# Nixie_ver1.net
KiCad netlist of a schematic drawn in EAGLE
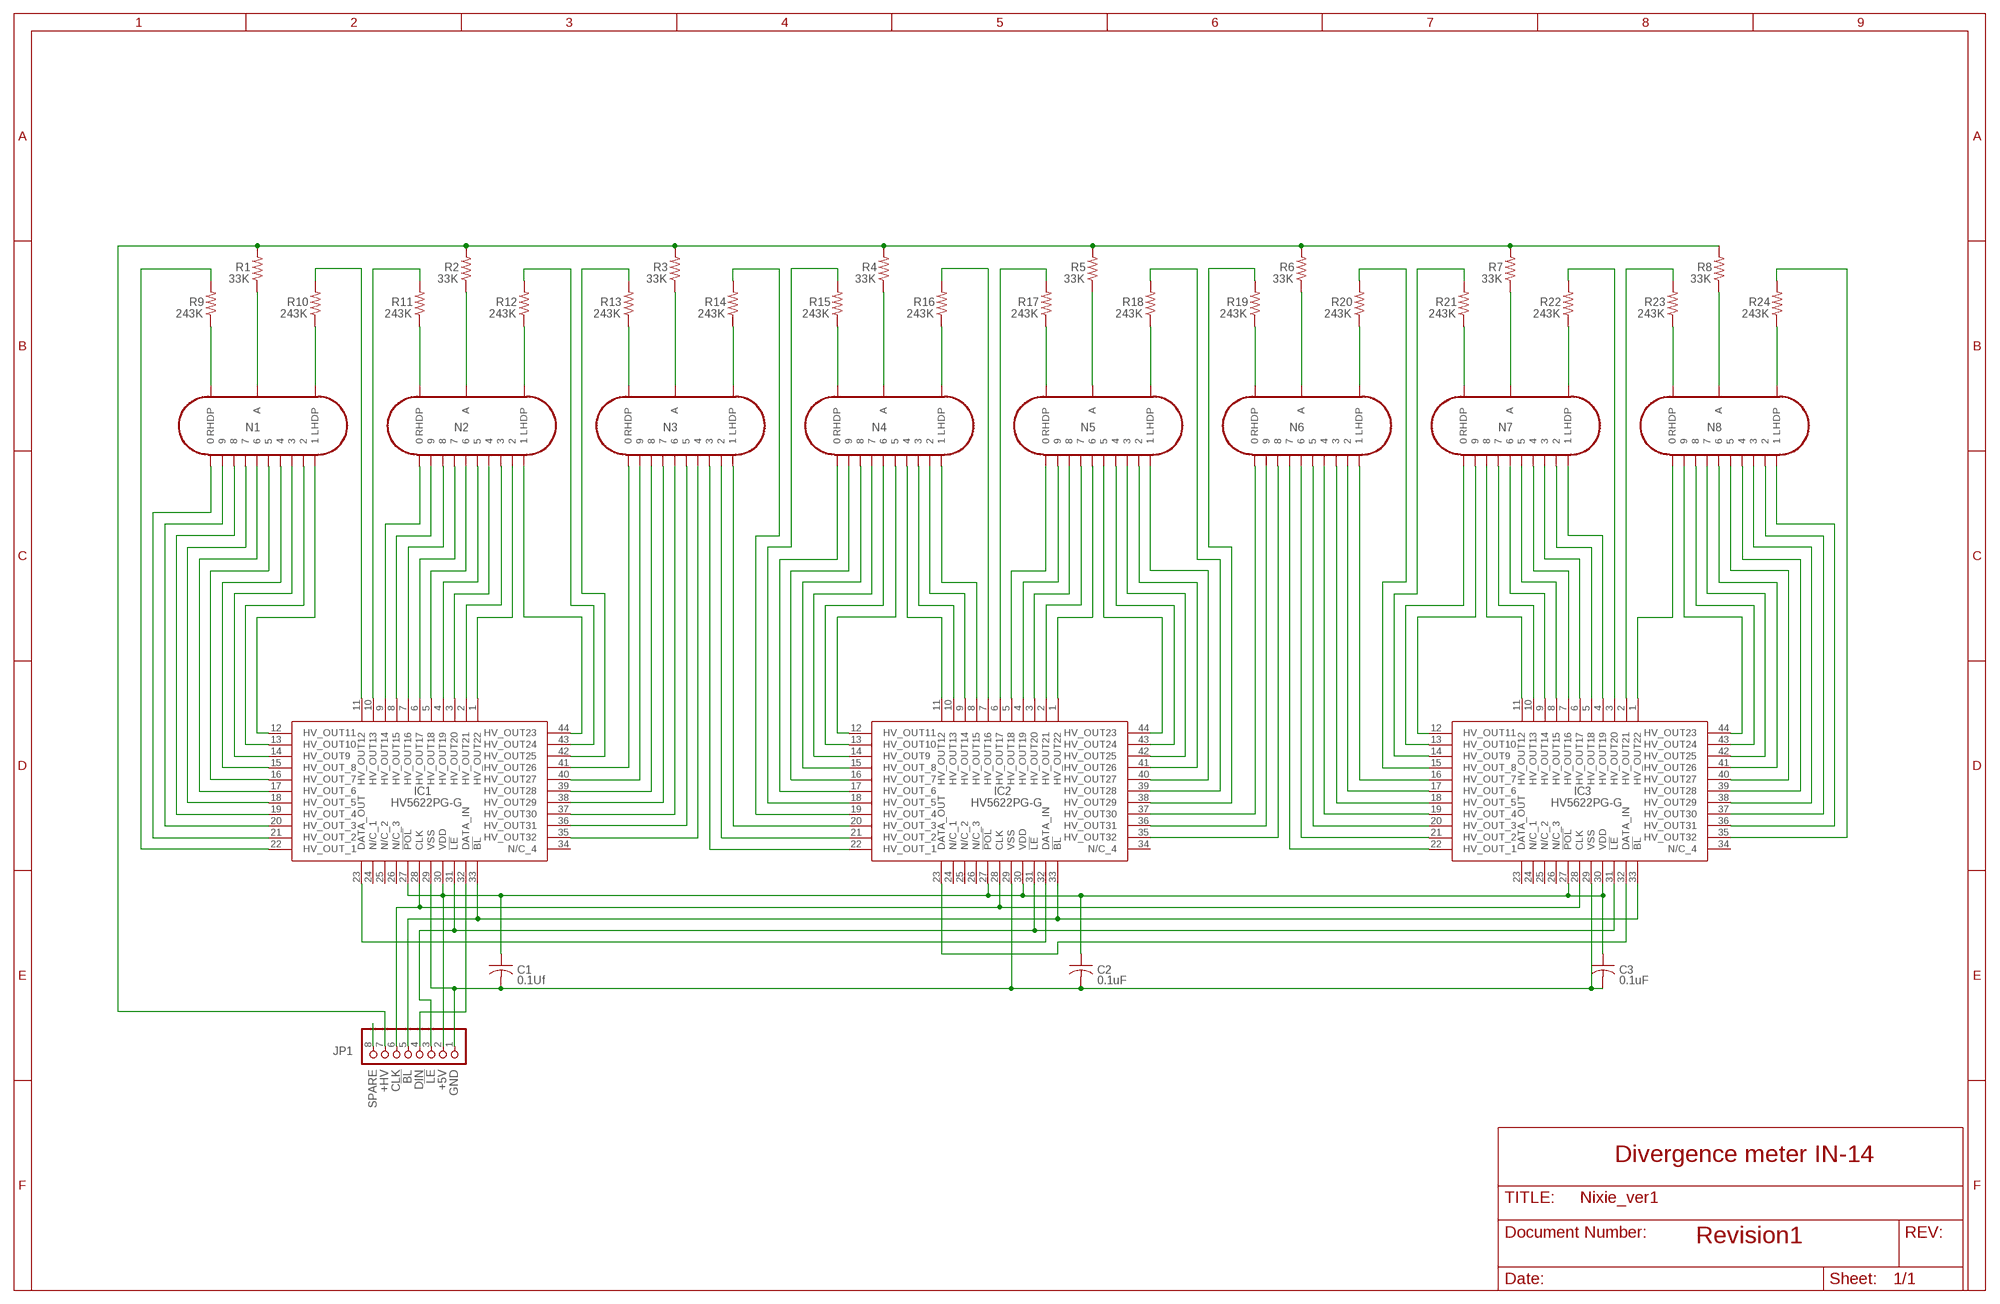
[diagram p0: schematic, sheet 1]

(export (version "E")
  (design (tool "Eeschema 10.0.6"))
  (components
    (comp (ref "C1")
      (value "0.1Uf")
      (footprint "eagle-import:C025-024X044")
      (libsource (lib "eagle-import") (part "C-US025-024X044"))
    )
    (comp (ref "C2")
      (value "0.1uF")
      (footprint "eagle-import:C025-024X044")
      (libsource (lib "eagle-import") (part "C-US025-024X044"))
    )
    (comp (ref "C3")
      (value "0.1uF")
      (footprint "eagle-import:C025-024X044")
      (libsource (lib "eagle-import") (part "C-US025-024X044"))
    )
    (comp (ref "IC1")
      (value "HV5622PG-G")
      (footprint "eagle-import:QFP80P1390X1390X235-44N")
      (fields (field (name "MOUSER_PART_NUMBER") "689-HV5622PG-G"))
      (libsource (lib "eagle-import") (part "HV5622PG-G"))
    )
    (comp (ref "IC2")
      (value "HV5622PG-G")
      (footprint "eagle-import:QFP80P1390X1390X235-44N")
      (fields (field (name "MOUSER_PART_NUMBER") "689-HV5622PG-G"))
      (libsource (lib "eagle-import") (part "HV5622PG-G"))
    )
    (comp (ref "IC3")
      (value "HV5622PG-G")
      (footprint "eagle-import:QFP80P1390X1390X235-44N")
      (fields (field (name "MOUSER_PART_NUMBER") "689-HV5622PG-G"))
      (libsource (lib "eagle-import") (part "HV5622PG-G"))
    )
    (comp (ref "JP1")
      (value "PINHD-1X8")
      (footprint "eagle-import:1X08")
      (libsource (lib "eagle-import") (part "PINHD-1X8"))
    )
    (comp (ref "N1")
      (value "IN-14")
      (footprint "eagle-import:IN-14")
      (libsource (lib "eagle-import") (part "IN-14"))
    )
    (comp (ref "N2")
      (value "IN-14")
      (footprint "eagle-import:IN-14")
      (libsource (lib "eagle-import") (part "IN-14"))
    )
    (comp (ref "N3")
      (value "IN-14")
      (footprint "eagle-import:IN-14")
      (libsource (lib "eagle-import") (part "IN-14"))
    )
    (comp (ref "N4")
      (value "IN-14")
      (footprint "eagle-import:IN-14")
      (libsource (lib "eagle-import") (part "IN-14"))
    )
    (comp (ref "N5")
      (value "IN-14")
      (footprint "eagle-import:IN-14")
      (libsource (lib "eagle-import") (part "IN-14"))
    )
    (comp (ref "N6")
      (value "IN-14")
      (footprint "eagle-import:IN-14")
      (libsource (lib "eagle-import") (part "IN-14"))
    )
    (comp (ref "N7")
      (value "IN-14")
      (footprint "eagle-import:IN-14")
      (libsource (lib "eagle-import") (part "IN-14"))
    )
    (comp (ref "N8")
      (value "IN-14")
      (footprint "eagle-import:IN-14")
      (libsource (lib "eagle-import") (part "IN-14"))
    )
    (comp (ref "R1")
      (value "33K")
      (footprint "eagle-import:0204_7")
      (libsource (lib "eagle-import") (part "R-US_0204/7"))
    )
    (comp (ref "R2")
      (value "33K")
      (footprint "eagle-import:0204_7")
      (libsource (lib "eagle-import") (part "R-US_0204/7"))
    )
    (comp (ref "R3")
      (value "33K")
      (footprint "eagle-import:0204_7")
      (libsource (lib "eagle-import") (part "R-US_0204/7"))
    )
    (comp (ref "R4")
      (value "33K")
      (footprint "eagle-import:0204_7")
      (libsource (lib "eagle-import") (part "R-US_0204/7"))
    )
    (comp (ref "R5")
      (value "33K")
      (footprint "eagle-import:0204_7")
      (libsource (lib "eagle-import") (part "R-US_0204/7"))
    )
    (comp (ref "R6")
      (value "33K")
      (footprint "eagle-import:0204_7")
      (libsource (lib "eagle-import") (part "R-US_0204/7"))
    )
    (comp (ref "R7")
      (value "33K")
      (footprint "eagle-import:0204_7")
      (libsource (lib "eagle-import") (part "R-US_0204/7"))
    )
    (comp (ref "R8")
      (value "33K")
      (footprint "eagle-import:0204_7")
      (libsource (lib "eagle-import") (part "R-US_0204/7"))
    )
    (comp (ref "R9")
      (value "243K")
      (footprint "eagle-import:0204_7")
      (libsource (lib "eagle-import") (part "R-US_0204/7"))
    )
    (comp (ref "R10")
      (value "243K")
      (footprint "eagle-import:0204_7")
      (libsource (lib "eagle-import") (part "R-US_0204/7"))
    )
    (comp (ref "R11")
      (value "243K")
      (footprint "eagle-import:0204_7")
      (libsource (lib "eagle-import") (part "R-US_0204/7"))
    )
    (comp (ref "R12")
      (value "243K")
      (footprint "eagle-import:0204_7")
      (libsource (lib "eagle-import") (part "R-US_0204/7"))
    )
    (comp (ref "R13")
      (value "243K")
      (footprint "eagle-import:0204_7")
      (libsource (lib "eagle-import") (part "R-US_0204/7"))
    )
    (comp (ref "R14")
      (value "243K")
      (footprint "eagle-import:0204_7")
      (libsource (lib "eagle-import") (part "R-US_0204/7"))
    )
    (comp (ref "R15")
      (value "243K")
      (footprint "eagle-import:0204_7")
      (libsource (lib "eagle-import") (part "R-US_0204/7"))
    )
    (comp (ref "R16")
      (value "243K")
      (footprint "eagle-import:0204_7")
      (libsource (lib "eagle-import") (part "R-US_0204/7"))
    )
    (comp (ref "R17")
      (value "243K")
      (footprint "eagle-import:0204_7")
      (libsource (lib "eagle-import") (part "R-US_0204/7"))
    )
    (comp (ref "R18")
      (value "243K")
      (footprint "eagle-import:0204_7")
      (libsource (lib "eagle-import") (part "R-US_0204/7"))
    )
    (comp (ref "R19")
      (value "243K")
      (footprint "eagle-import:0204_7")
      (libsource (lib "eagle-import") (part "R-US_0204/7"))
    )
    (comp (ref "R20")
      (value "243K")
      (footprint "eagle-import:0204_7")
      (libsource (lib "eagle-import") (part "R-US_0204/7"))
    )
    (comp (ref "R21")
      (value "243K")
      (footprint "eagle-import:0204_7")
      (libsource (lib "eagle-import") (part "R-US_0204/7"))
    )
    (comp (ref "R22")
      (value "243K")
      (footprint "eagle-import:0204_7")
      (libsource (lib "eagle-import") (part "R-US_0204/7"))
    )
    (comp (ref "R23")
      (value "243K")
      (footprint "eagle-import:0204_7")
      (libsource (lib "eagle-import") (part "R-US_0204/7"))
    )
    (comp (ref "R24")
      (value "243K")
      (footprint "eagle-import:0204_7")
      (libsource (lib "eagle-import") (part "R-US_0204/7"))
    )
  )
  (nets
    (net (code "1") (name "/+5V") (class "Default")
      (node (ref "C1") (pin "1") (pinfunction "1_1") (pintype "passive"))
      (node (ref "C2") (pin "1") (pinfunction "1_1") (pintype "passive"))
      (node (ref "C3") (pin "1") (pinfunction "1_1") (pintype "passive"))
      (node (ref "IC1") (pin "27") (pinfunction "~{POL}_27") (pintype "bidirectional"))
      (node (ref "IC1") (pin "30") (pinfunction "VDD_30") (pintype "bidirectional"))
      (node (ref "IC2") (pin "27") (pinfunction "~{POL}_27") (pintype "bidirectional"))
      (node (ref "IC2") (pin "30") (pinfunction "VDD_30") (pintype "bidirectional"))
      (node (ref "IC3") (pin "27") (pinfunction "~{POL}_27") (pintype "bidirectional"))
      (node (ref "IC3") (pin "30") (pinfunction "VDD_30") (pintype "bidirectional"))
      (node (ref "JP1") (pin "2") (pinfunction "2_2") (pintype "passive"))
    )
    (net (code "2") (name "/+HV") (class "Default")
      (node (ref "JP1") (pin "7") (pinfunction "7_7") (pintype "passive"))
      (node (ref "R1") (pin "2") (pinfunction "2_2") (pintype "passive"))
      (node (ref "R2") (pin "2") (pinfunction "2_2") (pintype "passive"))
      (node (ref "R3") (pin "2") (pinfunction "2_2") (pintype "passive"))
      (node (ref "R4") (pin "2") (pinfunction "2_2") (pintype "passive"))
      (node (ref "R5") (pin "2") (pinfunction "2_2") (pintype "passive"))
      (node (ref "R6") (pin "2") (pinfunction "2_2") (pintype "passive"))
      (node (ref "R7") (pin "2") (pinfunction "2_2") (pintype "passive"))
      (node (ref "R8") (pin "2") (pinfunction "2_2") (pintype "passive"))
    )
    (net (code "3") (name "/CLK") (class "Default")
      (node (ref "IC1") (pin "28") (pinfunction "CLK_28") (pintype "bidirectional"))
      (node (ref "IC2") (pin "28") (pinfunction "CLK_28") (pintype "bidirectional"))
      (node (ref "IC3") (pin "28") (pinfunction "CLK_28") (pintype "bidirectional"))
      (node (ref "JP1") (pin "6") (pinfunction "6_6") (pintype "passive"))
    )
    (net (code "4") (name "/DIN") (class "Default")
      (node (ref "IC1") (pin "32") (pinfunction "DATA_IN_32") (pintype "bidirectional"))
      (node (ref "JP1") (pin "4") (pinfunction "4_4") (pintype "passive"))
    )
    (net (code "5") (name "/GND") (class "Default")
      (node (ref "C1") (pin "2") (pinfunction "2_2") (pintype "passive"))
      (node (ref "C2") (pin "2") (pinfunction "2_2") (pintype "passive"))
      (node (ref "C3") (pin "2") (pinfunction "2_2") (pintype "passive"))
      (node (ref "IC1") (pin "29") (pinfunction "VSS_29") (pintype "bidirectional"))
      (node (ref "IC2") (pin "29") (pinfunction "VSS_29") (pintype "bidirectional"))
      (node (ref "IC3") (pin "29") (pinfunction "VSS_29") (pintype "bidirectional"))
      (node (ref "JP1") (pin "1") (pinfunction "1_1") (pintype "passive"))
    )
    (net (code "6") (name "/SPARE") (class "Default")
      (node (ref "JP1") (pin "8") (pinfunction "8_8") (pintype "passive"))
    )
    (net (code "7") (name "/~{BL}") (class "Default")
      (node (ref "IC1") (pin "33") (pinfunction "~{BL}_33") (pintype "bidirectional"))
      (node (ref "IC2") (pin "33") (pinfunction "~{BL}_33") (pintype "bidirectional"))
      (node (ref "IC3") (pin "33") (pinfunction "~{BL}_33") (pintype "bidirectional"))
      (node (ref "JP1") (pin "5") (pinfunction "5_5") (pintype "passive"))
    )
    (net (code "8") (name "/~{LE}") (class "Default")
      (node (ref "IC1") (pin "31") (pinfunction "~{LE}_31") (pintype "bidirectional"))
      (node (ref "IC2") (pin "31") (pinfunction "~{LE}_31") (pintype "bidirectional"))
      (node (ref "IC3") (pin "31") (pinfunction "~{LE}_31") (pintype "bidirectional"))
      (node (ref "JP1") (pin "3") (pinfunction "3_3") (pintype "passive"))
    )
    (net (code "9") (name "Net-(IC1-DATA_OUT)") (class "Default")
      (node (ref "IC1") (pin "23") (pinfunction "DATA_OUT_23") (pintype "bidirectional"))
      (node (ref "IC2") (pin "32") (pinfunction "DATA_IN_32") (pintype "bidirectional"))
    )
    (net (code "10") (name "Net-(IC1-HV_OUT9)") (class "Default")
      (node (ref "IC1") (pin "14") (pinfunction "HV_OUT9_14") (pintype "bidirectional"))
      (node (ref "N1") (pin "3") (pinfunction "3_3") (pintype "bidirectional"))
    )
    (net (code "11") (name "Net-(IC1-HV_OUT10)") (class "Default")
      (node (ref "IC1") (pin "13") (pinfunction "HV_OUT10_13") (pintype "bidirectional"))
      (node (ref "N1") (pin "2") (pinfunction "2_2") (pintype "bidirectional"))
    )
    (net (code "12") (name "Net-(IC1-HV_OUT11)") (class "Default")
      (node (ref "IC1") (pin "12") (pinfunction "HV_OUT11_12") (pintype "bidirectional"))
      (node (ref "N1") (pin "1") (pinfunction "1_1") (pintype "bidirectional"))
    )
    (net (code "13") (name "Net-(IC1-HV_OUT12)") (class "Default")
      (node (ref "IC1") (pin "11") (pinfunction "HV_OUT12_11") (pintype "bidirectional"))
      (node (ref "R10") (pin "2") (pinfunction "2_2") (pintype "passive"))
    )
    (net (code "14") (name "Net-(IC1-HV_OUT13)") (class "Default")
      (node (ref "IC1") (pin "10") (pinfunction "HV_OUT13_10") (pintype "bidirectional"))
      (node (ref "R11") (pin "2") (pinfunction "2_2") (pintype "passive"))
    )
    (net (code "15") (name "Net-(IC1-HV_OUT14)") (class "Default")
      (node (ref "IC1") (pin "9") (pinfunction "HV_OUT14_9") (pintype "bidirectional"))
      (node (ref "N2") (pin "0") (pinfunction "0_0") (pintype "bidirectional"))
    )
    (net (code "16") (name "Net-(IC1-HV_OUT15)") (class "Default")
      (node (ref "IC1") (pin "8") (pinfunction "HV_OUT15_8") (pintype "bidirectional"))
      (node (ref "N2") (pin "9") (pinfunction "9_9") (pintype "bidirectional"))
    )
    (net (code "17") (name "Net-(IC1-HV_OUT16)") (class "Default")
      (node (ref "IC1") (pin "7") (pinfunction "HV_OUT16_7") (pintype "bidirectional"))
      (node (ref "N2") (pin "8") (pinfunction "8_8") (pintype "bidirectional"))
    )
    (net (code "18") (name "Net-(IC1-HV_OUT17)") (class "Default")
      (node (ref "IC1") (pin "6") (pinfunction "HV_OUT17_6") (pintype "bidirectional"))
      (node (ref "N2") (pin "7") (pinfunction "7_7") (pintype "bidirectional"))
    )
    (net (code "19") (name "Net-(IC1-HV_OUT18)") (class "Default")
      (node (ref "IC1") (pin "5") (pinfunction "HV_OUT18_5") (pintype "bidirectional"))
      (node (ref "N2") (pin "6") (pinfunction "6_6") (pintype "bidirectional"))
    )
    (net (code "20") (name "Net-(IC1-HV_OUT19)") (class "Default")
      (node (ref "IC1") (pin "4") (pinfunction "HV_OUT19_4") (pintype "bidirectional"))
      (node (ref "N2") (pin "5") (pinfunction "5_5") (pintype "bidirectional"))
    )
    (net (code "21") (name "Net-(IC1-HV_OUT20)") (class "Default")
      (node (ref "IC1") (pin "3") (pinfunction "HV_OUT20_3") (pintype "bidirectional"))
      (node (ref "N2") (pin "4") (pinfunction "4_4") (pintype "bidirectional"))
    )
    (net (code "22") (name "Net-(IC1-HV_OUT21)") (class "Default")
      (node (ref "IC1") (pin "2") (pinfunction "HV_OUT21_2") (pintype "bidirectional"))
      (node (ref "N2") (pin "3") (pinfunction "3_3") (pintype "bidirectional"))
    )
    (net (code "23") (name "Net-(IC1-HV_OUT22)") (class "Default")
      (node (ref "IC1") (pin "1") (pinfunction "HV_OUT22_1") (pintype "bidirectional"))
      (node (ref "N2") (pin "2") (pinfunction "2_2") (pintype "bidirectional"))
    )
    (net (code "24") (name "Net-(IC1-HV_OUT23)") (class "Default")
      (node (ref "IC1") (pin "44") (pinfunction "HV_OUT23_44") (pintype "bidirectional"))
      (node (ref "N2") (pin "1") (pinfunction "1_1") (pintype "bidirectional"))
    )
    (net (code "25") (name "Net-(IC1-HV_OUT24)") (class "Default")
      (node (ref "IC1") (pin "43") (pinfunction "HV_OUT24_43") (pintype "bidirectional"))
      (node (ref "R12") (pin "2") (pinfunction "2_2") (pintype "passive"))
    )
    (net (code "26") (name "Net-(IC1-HV_OUT25)") (class "Default")
      (node (ref "IC1") (pin "42") (pinfunction "HV_OUT25_42") (pintype "bidirectional"))
      (node (ref "R13") (pin "2") (pinfunction "2_2") (pintype "passive"))
    )
    (net (code "27") (name "Net-(IC1-HV_OUT26)") (class "Default")
      (node (ref "IC1") (pin "41") (pinfunction "HV_OUT26_41") (pintype "bidirectional"))
      (node (ref "N3") (pin "0") (pinfunction "0_0") (pintype "bidirectional"))
    )
    (net (code "28") (name "Net-(IC1-HV_OUT27)") (class "Default")
      (node (ref "IC1") (pin "40") (pinfunction "HV_OUT27_40") (pintype "bidirectional"))
      (node (ref "N3") (pin "9") (pinfunction "9_9") (pintype "bidirectional"))
    )
    (net (code "29") (name "Net-(IC1-HV_OUT28)") (class "Default")
      (node (ref "IC1") (pin "39") (pinfunction "HV_OUT28_39") (pintype "bidirectional"))
      (node (ref "N3") (pin "8") (pinfunction "8_8") (pintype "bidirectional"))
    )
    (net (code "30") (name "Net-(IC1-HV_OUT29)") (class "Default")
      (node (ref "IC1") (pin "38") (pinfunction "HV_OUT29_38") (pintype "bidirectional"))
      (node (ref "N3") (pin "7") (pinfunction "7_7") (pintype "bidirectional"))
    )
    (net (code "31") (name "Net-(IC1-HV_OUT30)") (class "Default")
      (node (ref "IC1") (pin "37") (pinfunction "HV_OUT30_37") (pintype "bidirectional"))
      (node (ref "N3") (pin "6") (pinfunction "6_6") (pintype "bidirectional"))
    )
    (net (code "32") (name "Net-(IC1-HV_OUT31)") (class "Default")
      (node (ref "IC1") (pin "36") (pinfunction "HV_OUT31_36") (pintype "bidirectional"))
      (node (ref "N3") (pin "5") (pinfunction "5_5") (pintype "bidirectional"))
    )
    (net (code "33") (name "Net-(IC1-HV_OUT32)") (class "Default")
      (node (ref "IC1") (pin "35") (pinfunction "HV_OUT32_35") (pintype "bidirectional"))
      (node (ref "N3") (pin "4") (pinfunction "4_4") (pintype "bidirectional"))
    )
    (net (code "34") (name "Net-(IC1-HV_OUT_1)") (class "Default")
      (node (ref "IC1") (pin "22") (pinfunction "HV_OUT_1_22") (pintype "bidirectional"))
      (node (ref "R9") (pin "2") (pinfunction "2_2") (pintype "passive"))
    )
    (net (code "35") (name "Net-(IC1-HV_OUT_2)") (class "Default")
      (node (ref "IC1") (pin "21") (pinfunction "HV_OUT_2_21") (pintype "bidirectional"))
      (node (ref "N1") (pin "0") (pinfunction "0_0") (pintype "bidirectional"))
    )
    (net (code "36") (name "Net-(IC1-HV_OUT_3)") (class "Default")
      (node (ref "IC1") (pin "20") (pinfunction "HV_OUT_3_20") (pintype "bidirectional"))
      (node (ref "N1") (pin "9") (pinfunction "9_9") (pintype "bidirectional"))
    )
    (net (code "37") (name "Net-(IC1-HV_OUT_4)") (class "Default")
      (node (ref "IC1") (pin "19") (pinfunction "HV_OUT_4_19") (pintype "bidirectional"))
      (node (ref "N1") (pin "8") (pinfunction "8_8") (pintype "bidirectional"))
    )
    (net (code "38") (name "Net-(IC1-HV_OUT_5)") (class "Default")
      (node (ref "IC1") (pin "18") (pinfunction "HV_OUT_5_18") (pintype "bidirectional"))
      (node (ref "N1") (pin "7") (pinfunction "7_7") (pintype "bidirectional"))
    )
    (net (code "39") (name "Net-(IC1-HV_OUT_6)") (class "Default")
      (node (ref "IC1") (pin "17") (pinfunction "HV_OUT_6_17") (pintype "bidirectional"))
      (node (ref "N1") (pin "6") (pinfunction "6_6") (pintype "bidirectional"))
    )
    (net (code "40") (name "Net-(IC1-HV_OUT_7)") (class "Default")
      (node (ref "IC1") (pin "16") (pinfunction "HV_OUT_7_16") (pintype "bidirectional"))
      (node (ref "N1") (pin "5") (pinfunction "5_5") (pintype "bidirectional"))
    )
    (net (code "41") (name "Net-(IC1-HV_OUT_8)") (class "Default")
      (node (ref "IC1") (pin "15") (pinfunction "HV_OUT_8_15") (pintype "bidirectional"))
      (node (ref "N1") (pin "4") (pinfunction "4_4") (pintype "bidirectional"))
    )
    (net (code "42") (name "Net-(IC2-DATA_OUT)") (class "Default")
      (node (ref "IC2") (pin "23") (pinfunction "DATA_OUT_23") (pintype "bidirectional"))
      (node (ref "IC3") (pin "32") (pinfunction "DATA_IN_32") (pintype "bidirectional"))
    )
    (net (code "43") (name "Net-(IC2-HV_OUT9)") (class "Default")
      (node (ref "IC2") (pin "14") (pinfunction "HV_OUT9_14") (pintype "bidirectional"))
      (node (ref "N4") (pin "7") (pinfunction "7_7") (pintype "bidirectional"))
    )
    (net (code "44") (name "Net-(IC2-HV_OUT10)") (class "Default")
      (node (ref "IC2") (pin "13") (pinfunction "HV_OUT10_13") (pintype "bidirectional"))
      (node (ref "N4") (pin "6") (pinfunction "6_6") (pintype "bidirectional"))
    )
    (net (code "45") (name "Net-(IC2-HV_OUT11)") (class "Default")
      (node (ref "IC2") (pin "12") (pinfunction "HV_OUT11_12") (pintype "bidirectional"))
      (node (ref "N4") (pin "5") (pinfunction "5_5") (pintype "bidirectional"))
    )
    (net (code "46") (name "Net-(IC2-HV_OUT12)") (class "Default")
      (node (ref "IC2") (pin "11") (pinfunction "HV_OUT12_11") (pintype "bidirectional"))
      (node (ref "N4") (pin "4") (pinfunction "4_4") (pintype "bidirectional"))
    )
    (net (code "47") (name "Net-(IC2-HV_OUT13)") (class "Default")
      (node (ref "IC2") (pin "10") (pinfunction "HV_OUT13_10") (pintype "bidirectional"))
      (node (ref "N4") (pin "3") (pinfunction "3_3") (pintype "bidirectional"))
    )
    (net (code "48") (name "Net-(IC2-HV_OUT14)") (class "Default")
      (node (ref "IC2") (pin "9") (pinfunction "HV_OUT14_9") (pintype "bidirectional"))
      (node (ref "N4") (pin "2") (pinfunction "2_2") (pintype "bidirectional"))
    )
    (net (code "49") (name "Net-(IC2-HV_OUT15)") (class "Default")
      (node (ref "IC2") (pin "8") (pinfunction "HV_OUT15_8") (pintype "bidirectional"))
      (node (ref "N4") (pin "1") (pinfunction "1_1") (pintype "bidirectional"))
    )
    (net (code "50") (name "Net-(IC2-HV_OUT16)") (class "Default")
      (node (ref "IC2") (pin "7") (pinfunction "HV_OUT16_7") (pintype "bidirectional"))
      (node (ref "R16") (pin "2") (pinfunction "2_2") (pintype "passive"))
    )
    (net (code "51") (name "Net-(IC2-HV_OUT17)") (class "Default")
      (node (ref "IC2") (pin "6") (pinfunction "HV_OUT17_6") (pintype "bidirectional"))
      (node (ref "R17") (pin "2") (pinfunction "2_2") (pintype "passive"))
    )
    (net (code "52") (name "Net-(IC2-HV_OUT18)") (class "Default")
      (node (ref "IC2") (pin "5") (pinfunction "HV_OUT18_5") (pintype "bidirectional"))
      (node (ref "N5") (pin "0") (pinfunction "0_0") (pintype "bidirectional"))
    )
    (net (code "53") (name "Net-(IC2-HV_OUT19)") (class "Default")
      (node (ref "IC2") (pin "4") (pinfunction "HV_OUT19_4") (pintype "bidirectional"))
      (node (ref "N5") (pin "9") (pinfunction "9_9") (pintype "bidirectional"))
    )
    (net (code "54") (name "Net-(IC2-HV_OUT20)") (class "Default")
      (node (ref "IC2") (pin "3") (pinfunction "HV_OUT20_3") (pintype "bidirectional"))
      (node (ref "N5") (pin "8") (pinfunction "8_8") (pintype "bidirectional"))
    )
    (net (code "55") (name "Net-(IC2-HV_OUT21)") (class "Default")
      (node (ref "IC2") (pin "2") (pinfunction "HV_OUT21_2") (pintype "bidirectional"))
      (node (ref "N5") (pin "7") (pinfunction "7_7") (pintype "bidirectional"))
    )
    (net (code "56") (name "Net-(IC2-HV_OUT22)") (class "Default")
      (node (ref "IC2") (pin "1") (pinfunction "HV_OUT22_1") (pintype "bidirectional"))
      (node (ref "N5") (pin "6") (pinfunction "6_6") (pintype "bidirectional"))
    )
    (net (code "57") (name "Net-(IC2-HV_OUT23)") (class "Default")
      (node (ref "IC2") (pin "44") (pinfunction "HV_OUT23_44") (pintype "bidirectional"))
      (node (ref "N5") (pin "5") (pinfunction "5_5") (pintype "bidirectional"))
    )
    (net (code "58") (name "Net-(IC2-HV_OUT24)") (class "Default")
      (node (ref "IC2") (pin "43") (pinfunction "HV_OUT24_43") (pintype "bidirectional"))
      (node (ref "N5") (pin "4") (pinfunction "4_4") (pintype "bidirectional"))
    )
    (net (code "59") (name "Net-(IC2-HV_OUT25)") (class "Default")
      (node (ref "IC2") (pin "42") (pinfunction "HV_OUT25_42") (pintype "bidirectional"))
      (node (ref "N5") (pin "3") (pinfunction "3_3") (pintype "bidirectional"))
    )
    (net (code "60") (name "Net-(IC2-HV_OUT26)") (class "Default")
      (node (ref "IC2") (pin "41") (pinfunction "HV_OUT26_41") (pintype "bidirectional"))
      (node (ref "N5") (pin "2") (pinfunction "2_2") (pintype "bidirectional"))
    )
    (net (code "61") (name "Net-(IC2-HV_OUT27)") (class "Default")
      (node (ref "IC2") (pin "40") (pinfunction "HV_OUT27_40") (pintype "bidirectional"))
      (node (ref "N5") (pin "1") (pinfunction "1_1") (pintype "bidirectional"))
    )
    (net (code "62") (name "Net-(IC2-HV_OUT28)") (class "Default")
      (node (ref "IC2") (pin "39") (pinfunction "HV_OUT28_39") (pintype "bidirectional"))
      (node (ref "R18") (pin "2") (pinfunction "2_2") (pintype "passive"))
    )
    (net (code "63") (name "Net-(IC2-HV_OUT29)") (class "Default")
      (node (ref "IC2") (pin "38") (pinfunction "HV_OUT29_38") (pintype "bidirectional"))
      (node (ref "R19") (pin "2") (pinfunction "2_2") (pintype "passive"))
    )
    (net (code "64") (name "Net-(IC2-HV_OUT30)") (class "Default")
      (node (ref "IC2") (pin "37") (pinfunction "HV_OUT30_37") (pintype "bidirectional"))
      (node (ref "N6") (pin "0") (pinfunction "0_0") (pintype "bidirectional"))
    )
    (net (code "65") (name "Net-(IC2-HV_OUT31)") (class "Default")
      (node (ref "IC2") (pin "36") (pinfunction "HV_OUT31_36") (pintype "bidirectional"))
      (node (ref "N6") (pin "9") (pinfunction "9_9") (pintype "bidirectional"))
    )
    (net (code "66") (name "Net-(IC2-HV_OUT32)") (class "Default")
      (node (ref "IC2") (pin "35") (pinfunction "HV_OUT32_35") (pintype "bidirectional"))
      (node (ref "N6") (pin "8") (pinfunction "8_8") (pintype "bidirectional"))
    )
    (net (code "67") (name "Net-(IC2-HV_OUT_1)") (class "Default")
      (node (ref "IC2") (pin "22") (pinfunction "HV_OUT_1_22") (pintype "bidirectional"))
      (node (ref "N3") (pin "3") (pinfunction "3_3") (pintype "bidirectional"))
    )
    (net (code "68") (name "Net-(IC2-HV_OUT_2)") (class "Default")
      (node (ref "IC2") (pin "21") (pinfunction "HV_OUT_2_21") (pintype "bidirectional"))
      (node (ref "N3") (pin "2") (pinfunction "2_2") (pintype "bidirectional"))
    )
    (net (code "69") (name "Net-(IC2-HV_OUT_3)") (class "Default")
      (node (ref "IC2") (pin "20") (pinfunction "HV_OUT_3_20") (pintype "bidirectional"))
      (node (ref "N3") (pin "1") (pinfunction "1_1") (pintype "bidirectional"))
    )
    (net (code "70") (name "Net-(IC2-HV_OUT_4)") (class "Default")
      (node (ref "IC2") (pin "19") (pinfunction "HV_OUT_4_19") (pintype "bidirectional"))
      (node (ref "R14") (pin "2") (pinfunction "2_2") (pintype "passive"))
    )
    (net (code "71") (name "Net-(IC2-HV_OUT_5)") (class "Default")
      (node (ref "IC2") (pin "18") (pinfunction "HV_OUT_5_18") (pintype "bidirectional"))
      (node (ref "R15") (pin "2") (pinfunction "2_2") (pintype "passive"))
    )
    (net (code "72") (name "Net-(IC2-HV_OUT_6)") (class "Default")
      (node (ref "IC2") (pin "17") (pinfunction "HV_OUT_6_17") (pintype "bidirectional"))
      (node (ref "N4") (pin "0") (pinfunction "0_0") (pintype "bidirectional"))
    )
    (net (code "73") (name "Net-(IC2-HV_OUT_7)") (class "Default")
      (node (ref "IC2") (pin "16") (pinfunction "HV_OUT_7_16") (pintype "bidirectional"))
      (node (ref "N4") (pin "9") (pinfunction "9_9") (pintype "bidirectional"))
    )
    (net (code "74") (name "Net-(IC2-HV_OUT_8)") (class "Default")
      (node (ref "IC2") (pin "15") (pinfunction "HV_OUT_8_15") (pintype "bidirectional"))
      (node (ref "N4") (pin "8") (pinfunction "8_8") (pintype "bidirectional"))
    )
    (net (code "75") (name "Net-(IC3-HV_OUT9)") (class "Default")
      (node (ref "IC3") (pin "14") (pinfunction "HV_OUT9_14") (pintype "bidirectional"))
      (node (ref "R21") (pin "2") (pinfunction "2_2") (pintype "passive"))
    )
    (net (code "76") (name "Net-(IC3-HV_OUT10)") (class "Default")
      (node (ref "IC3") (pin "13") (pinfunction "HV_OUT10_13") (pintype "bidirectional"))
      (node (ref "N7") (pin "0") (pinfunction "0_0") (pintype "bidirectional"))
    )
    (net (code "77") (name "Net-(IC3-HV_OUT11)") (class "Default")
      (node (ref "IC3") (pin "12") (pinfunction "HV_OUT11_12") (pintype "bidirectional"))
      (node (ref "N7") (pin "9") (pinfunction "9_9") (pintype "bidirectional"))
    )
    (net (code "78") (name "Net-(IC3-HV_OUT12)") (class "Default")
      (node (ref "IC3") (pin "11") (pinfunction "HV_OUT12_11") (pintype "bidirectional"))
      (node (ref "N7") (pin "8") (pinfunction "8_8") (pintype "bidirectional"))
    )
    (net (code "79") (name "Net-(IC3-HV_OUT13)") (class "Default")
      (node (ref "IC3") (pin "10") (pinfunction "HV_OUT13_10") (pintype "bidirectional"))
      (node (ref "N7") (pin "7") (pinfunction "7_7") (pintype "bidirectional"))
    )
    (net (code "80") (name "Net-(IC3-HV_OUT14)") (class "Default")
      (node (ref "IC3") (pin "9") (pinfunction "HV_OUT14_9") (pintype "bidirectional"))
      (node (ref "N7") (pin "6") (pinfunction "6_6") (pintype "bidirectional"))
    )
    (net (code "81") (name "Net-(IC3-HV_OUT15)") (class "Default")
      (node (ref "IC3") (pin "8") (pinfunction "HV_OUT15_8") (pintype "bidirectional"))
      (node (ref "N7") (pin "5") (pinfunction "5_5") (pintype "bidirectional"))
    )
    (net (code "82") (name "Net-(IC3-HV_OUT16)") (class "Default")
      (node (ref "IC3") (pin "7") (pinfunction "HV_OUT16_7") (pintype "bidirectional"))
      (node (ref "N7") (pin "4") (pinfunction "4_4") (pintype "bidirectional"))
    )
    (net (code "83") (name "Net-(IC3-HV_OUT17)") (class "Default")
      (node (ref "IC3") (pin "6") (pinfunction "HV_OUT17_6") (pintype "bidirectional"))
      (node (ref "N7") (pin "3") (pinfunction "3_3") (pintype "bidirectional"))
    )
    (net (code "84") (name "Net-(IC3-HV_OUT18)") (class "Default")
      (node (ref "IC3") (pin "5") (pinfunction "HV_OUT18_5") (pintype "bidirectional"))
      (node (ref "N7") (pin "2") (pinfunction "2_2") (pintype "bidirectional"))
    )
    (net (code "85") (name "Net-(IC3-HV_OUT19)") (class "Default")
      (node (ref "IC3") (pin "4") (pinfunction "HV_OUT19_4") (pintype "bidirectional"))
      (node (ref "N7") (pin "1") (pinfunction "1_1") (pintype "bidirectional"))
    )
    (net (code "86") (name "Net-(IC3-HV_OUT20)") (class "Default")
      (node (ref "IC3") (pin "3") (pinfunction "HV_OUT20_3") (pintype "bidirectional"))
      (node (ref "R22") (pin "2") (pinfunction "2_2") (pintype "passive"))
    )
    (net (code "87") (name "Net-(IC3-HV_OUT21)") (class "Default")
      (node (ref "IC3") (pin "2") (pinfunction "HV_OUT21_2") (pintype "bidirectional"))
      (node (ref "R23") (pin "2") (pinfunction "2_2") (pintype "passive"))
    )
    (net (code "88") (name "Net-(IC3-HV_OUT22)") (class "Default")
      (node (ref "IC3") (pin "1") (pinfunction "HV_OUT22_1") (pintype "bidirectional"))
      (node (ref "N8") (pin "0") (pinfunction "0_0") (pintype "bidirectional"))
    )
    (net (code "89") (name "Net-(IC3-HV_OUT23)") (class "Default")
      (node (ref "IC3") (pin "44") (pinfunction "HV_OUT23_44") (pintype "bidirectional"))
      (node (ref "N8") (pin "9") (pinfunction "9_9") (pintype "bidirectional"))
    )
    (net (code "90") (name "Net-(IC3-HV_OUT24)") (class "Default")
      (node (ref "IC3") (pin "43") (pinfunction "HV_OUT24_43") (pintype "bidirectional"))
      (node (ref "N8") (pin "8") (pinfunction "8_8") (pintype "bidirectional"))
    )
    (net (code "91") (name "Net-(IC3-HV_OUT25)") (class "Default")
      (node (ref "IC3") (pin "42") (pinfunction "HV_OUT25_42") (pintype "bidirectional"))
      (node (ref "N8") (pin "7") (pinfunction "7_7") (pintype "bidirectional"))
    )
    (net (code "92") (name "Net-(IC3-HV_OUT26)") (class "Default")
      (node (ref "IC3") (pin "41") (pinfunction "HV_OUT26_41") (pintype "bidirectional"))
      (node (ref "N8") (pin "6") (pinfunction "6_6") (pintype "bidirectional"))
    )
    (net (code "93") (name "Net-(IC3-HV_OUT27)") (class "Default")
      (node (ref "IC3") (pin "40") (pinfunction "HV_OUT27_40") (pintype "bidirectional"))
      (node (ref "N8") (pin "5") (pinfunction "5_5") (pintype "bidirectional"))
    )
    (net (code "94") (name "Net-(IC3-HV_OUT28)") (class "Default")
      (node (ref "IC3") (pin "39") (pinfunction "HV_OUT28_39") (pintype "bidirectional"))
      (node (ref "N8") (pin "4") (pinfunction "4_4") (pintype "bidirectional"))
    )
    (net (code "95") (name "Net-(IC3-HV_OUT29)") (class "Default")
      (node (ref "IC3") (pin "38") (pinfunction "HV_OUT29_38") (pintype "bidirectional"))
      (node (ref "N8") (pin "3") (pinfunction "3_3") (pintype "bidirectional"))
    )
    (net (code "96") (name "Net-(IC3-HV_OUT30)") (class "Default")
      (node (ref "IC3") (pin "37") (pinfunction "HV_OUT30_37") (pintype "bidirectional"))
      (node (ref "N8") (pin "2") (pinfunction "2_2") (pintype "bidirectional"))
    )
    (net (code "97") (name "Net-(IC3-HV_OUT31)") (class "Default")
      (node (ref "IC3") (pin "36") (pinfunction "HV_OUT31_36") (pintype "bidirectional"))
      (node (ref "N8") (pin "1") (pinfunction "1_1") (pintype "bidirectional"))
    )
    (net (code "98") (name "Net-(IC3-HV_OUT32)") (class "Default")
      (node (ref "IC3") (pin "35") (pinfunction "HV_OUT32_35") (pintype "bidirectional"))
      (node (ref "R24") (pin "2") (pinfunction "2_2") (pintype "passive"))
    )
    (net (code "99") (name "Net-(IC3-HV_OUT_1)") (class "Default")
      (node (ref "IC3") (pin "22") (pinfunction "HV_OUT_1_22") (pintype "bidirectional"))
      (node (ref "N6") (pin "7") (pinfunction "7_7") (pintype "bidirectional"))
    )
    (net (code "100") (name "Net-(IC3-HV_OUT_2)") (class "Default")
      (node (ref "IC3") (pin "21") (pinfunction "HV_OUT_2_21") (pintype "bidirectional"))
      (node (ref "N6") (pin "6") (pinfunction "6_6") (pintype "bidirectional"))
    )
    (net (code "101") (name "Net-(IC3-HV_OUT_3)") (class "Default")
      (node (ref "IC3") (pin "20") (pinfunction "HV_OUT_3_20") (pintype "bidirectional"))
      (node (ref "N6") (pin "5") (pinfunction "5_5") (pintype "bidirectional"))
    )
    (net (code "102") (name "Net-(IC3-HV_OUT_4)") (class "Default")
      (node (ref "IC3") (pin "19") (pinfunction "HV_OUT_4_19") (pintype "bidirectional"))
      (node (ref "N6") (pin "4") (pinfunction "4_4") (pintype "bidirectional"))
    )
    (net (code "103") (name "Net-(IC3-HV_OUT_5)") (class "Default")
      (node (ref "IC3") (pin "18") (pinfunction "HV_OUT_5_18") (pintype "bidirectional"))
      (node (ref "N6") (pin "3") (pinfunction "3_3") (pintype "bidirectional"))
    )
    (net (code "104") (name "Net-(IC3-HV_OUT_6)") (class "Default")
      (node (ref "IC3") (pin "17") (pinfunction "HV_OUT_6_17") (pintype "bidirectional"))
      (node (ref "N6") (pin "2") (pinfunction "2_2") (pintype "bidirectional"))
    )
    (net (code "105") (name "Net-(IC3-HV_OUT_7)") (class "Default")
      (node (ref "IC3") (pin "16") (pinfunction "HV_OUT_7_16") (pintype "bidirectional"))
      (node (ref "N6") (pin "1") (pinfunction "1_1") (pintype "bidirectional"))
    )
    (net (code "106") (name "Net-(IC3-HV_OUT_8)") (class "Default")
      (node (ref "IC3") (pin "15") (pinfunction "HV_OUT_8_15") (pintype "bidirectional"))
      (node (ref "R20") (pin "2") (pinfunction "2_2") (pintype "passive"))
    )
    (net (code "107") (name "Net-(N1-PadA)") (class "Default")
      (node (ref "N1") (pin "A") (pinfunction "A_A") (pintype "bidirectional"))
      (node (ref "R1") (pin "1") (pinfunction "1_1") (pintype "passive"))
    )
    (net (code "108") (name "Net-(N1-PadLHDP)") (class "Default")
      (node (ref "N1") (pin "LHDP") (pinfunction "LHDP_LHDP") (pintype "bidirectional"))
      (node (ref "R10") (pin "1") (pinfunction "1_1") (pintype "passive"))
    )
    (net (code "109") (name "Net-(N1-PadRHDP)") (class "Default")
      (node (ref "N1") (pin "RHDP") (pinfunction "RHDP_RHDP") (pintype "bidirectional"))
      (node (ref "R9") (pin "1") (pinfunction "1_1") (pintype "passive"))
    )
    (net (code "110") (name "Net-(N2-PadA)") (class "Default")
      (node (ref "N2") (pin "A") (pinfunction "A_A") (pintype "bidirectional"))
      (node (ref "R2") (pin "1") (pinfunction "1_1") (pintype "passive"))
    )
    (net (code "111") (name "Net-(N2-PadLHDP)") (class "Default")
      (node (ref "N2") (pin "LHDP") (pinfunction "LHDP_LHDP") (pintype "bidirectional"))
      (node (ref "R12") (pin "1") (pinfunction "1_1") (pintype "passive"))
    )
    (net (code "112") (name "Net-(N2-PadRHDP)") (class "Default")
      (node (ref "N2") (pin "RHDP") (pinfunction "RHDP_RHDP") (pintype "bidirectional"))
      (node (ref "R11") (pin "1") (pinfunction "1_1") (pintype "passive"))
    )
    (net (code "113") (name "Net-(N3-PadA)") (class "Default")
      (node (ref "N3") (pin "A") (pinfunction "A_A") (pintype "bidirectional"))
      (node (ref "R3") (pin "1") (pinfunction "1_1") (pintype "passive"))
    )
    (net (code "114") (name "Net-(N3-PadLHDP)") (class "Default")
      (node (ref "N3") (pin "LHDP") (pinfunction "LHDP_LHDP") (pintype "bidirectional"))
      (node (ref "R14") (pin "1") (pinfunction "1_1") (pintype "passive"))
    )
    (net (code "115") (name "Net-(N3-PadRHDP)") (class "Default")
      (node (ref "N3") (pin "RHDP") (pinfunction "RHDP_RHDP") (pintype "bidirectional"))
      (node (ref "R13") (pin "1") (pinfunction "1_1") (pintype "passive"))
    )
    (net (code "116") (name "Net-(N4-PadA)") (class "Default")
      (node (ref "N4") (pin "A") (pinfunction "A_A") (pintype "bidirectional"))
      (node (ref "R4") (pin "1") (pinfunction "1_1") (pintype "passive"))
    )
    (net (code "117") (name "Net-(N4-PadLHDP)") (class "Default")
      (node (ref "N4") (pin "LHDP") (pinfunction "LHDP_LHDP") (pintype "bidirectional"))
      (node (ref "R16") (pin "1") (pinfunction "1_1") (pintype "passive"))
    )
    (net (code "118") (name "Net-(N4-PadRHDP)") (class "Default")
      (node (ref "N4") (pin "RHDP") (pinfunction "RHDP_RHDP") (pintype "bidirectional"))
      (node (ref "R15") (pin "1") (pinfunction "1_1") (pintype "passive"))
    )
    (net (code "119") (name "Net-(N5-PadA)") (class "Default")
      (node (ref "N5") (pin "A") (pinfunction "A_A") (pintype "bidirectional"))
      (node (ref "R5") (pin "1") (pinfunction "1_1") (pintype "passive"))
    )
    (net (code "120") (name "Net-(N5-PadLHDP)") (class "Default")
      (node (ref "N5") (pin "LHDP") (pinfunction "LHDP_LHDP") (pintype "bidirectional"))
      (node (ref "R18") (pin "1") (pinfunction "1_1") (pintype "passive"))
    )
    (net (code "121") (name "Net-(N5-PadRHDP)") (class "Default")
      (node (ref "N5") (pin "RHDP") (pinfunction "RHDP_RHDP") (pintype "bidirectional"))
      (node (ref "R17") (pin "1") (pinfunction "1_1") (pintype "passive"))
    )
    (net (code "122") (name "Net-(N6-PadA)") (class "Default")
      (node (ref "N6") (pin "A") (pinfunction "A_A") (pintype "bidirectional"))
      (node (ref "R6") (pin "1") (pinfunction "1_1") (pintype "passive"))
    )
    (net (code "123") (name "Net-(N6-PadLHDP)") (class "Default")
      (node (ref "N6") (pin "LHDP") (pinfunction "LHDP_LHDP") (pintype "bidirectional"))
      (node (ref "R20") (pin "1") (pinfunction "1_1") (pintype "passive"))
    )
    (net (code "124") (name "Net-(N6-PadRHDP)") (class "Default")
      (node (ref "N6") (pin "RHDP") (pinfunction "RHDP_RHDP") (pintype "bidirectional"))
      (node (ref "R19") (pin "1") (pinfunction "1_1") (pintype "passive"))
    )
    (net (code "125") (name "Net-(N7-PadA)") (class "Default")
      (node (ref "N7") (pin "A") (pinfunction "A_A") (pintype "bidirectional"))
      (node (ref "R7") (pin "1") (pinfunction "1_1") (pintype "passive"))
    )
    (net (code "126") (name "Net-(N7-PadLHDP)") (class "Default")
      (node (ref "N7") (pin "LHDP") (pinfunction "LHDP_LHDP") (pintype "bidirectional"))
      (node (ref "R22") (pin "1") (pinfunction "1_1") (pintype "passive"))
    )
    (net (code "127") (name "Net-(N7-PadRHDP)") (class "Default")
      (node (ref "N7") (pin "RHDP") (pinfunction "RHDP_RHDP") (pintype "bidirectional"))
      (node (ref "R21") (pin "1") (pinfunction "1_1") (pintype "passive"))
    )
    (net (code "128") (name "Net-(N8-PadA)") (class "Default")
      (node (ref "N8") (pin "A") (pinfunction "A_A") (pintype "bidirectional"))
      (node (ref "R8") (pin "1") (pinfunction "1_1") (pintype "passive"))
    )
    (net (code "129") (name "Net-(N8-PadLHDP)") (class "Default")
      (node (ref "N8") (pin "LHDP") (pinfunction "LHDP_LHDP") (pintype "bidirectional"))
      (node (ref "R24") (pin "1") (pinfunction "1_1") (pintype "passive"))
    )
    (net (code "130") (name "Net-(N8-PadRHDP)") (class "Default")
      (node (ref "N8") (pin "RHDP") (pinfunction "RHDP_RHDP") (pintype "bidirectional"))
      (node (ref "R23") (pin "1") (pinfunction "1_1") (pintype "passive"))
    )
    (net (code "131") (name "unconnected-(IC1-N{slash}C_1-Pad24)") (class "Default")
      (node (ref "IC1") (pin "24") (pinfunction "N/C_1_24") (pintype "bidirectional"))
    )
    (net (code "132") (name "unconnected-(IC1-N{slash}C_2-Pad25)") (class "Default")
      (node (ref "IC1") (pin "25") (pinfunction "N/C_2_25") (pintype "bidirectional"))
    )
    (net (code "133") (name "unconnected-(IC1-N{slash}C_3-Pad26)") (class "Default")
      (node (ref "IC1") (pin "26") (pinfunction "N/C_3_26") (pintype "bidirectional"))
    )
    (net (code "134") (name "unconnected-(IC1-N{slash}C_4-Pad34)") (class "Default")
      (node (ref "IC1") (pin "34") (pinfunction "N/C_4_34") (pintype "bidirectional"))
    )
    (net (code "135") (name "unconnected-(IC2-N{slash}C_1-Pad24)") (class "Default")
      (node (ref "IC2") (pin "24") (pinfunction "N/C_1_24") (pintype "bidirectional"))
    )
    (net (code "136") (name "unconnected-(IC2-N{slash}C_2-Pad25)") (class "Default")
      (node (ref "IC2") (pin "25") (pinfunction "N/C_2_25") (pintype "bidirectional"))
    )
    (net (code "137") (name "unconnected-(IC2-N{slash}C_3-Pad26)") (class "Default")
      (node (ref "IC2") (pin "26") (pinfunction "N/C_3_26") (pintype "bidirectional"))
    )
    (net (code "138") (name "unconnected-(IC2-N{slash}C_4-Pad34)") (class "Default")
      (node (ref "IC2") (pin "34") (pinfunction "N/C_4_34") (pintype "bidirectional"))
    )
    (net (code "139") (name "unconnected-(IC3-DATA_OUT-Pad23)") (class "Default")
      (node (ref "IC3") (pin "23") (pinfunction "DATA_OUT_23") (pintype "bidirectional"))
    )
    (net (code "140") (name "unconnected-(IC3-N{slash}C_1-Pad24)") (class "Default")
      (node (ref "IC3") (pin "24") (pinfunction "N/C_1_24") (pintype "bidirectional"))
    )
    (net (code "141") (name "unconnected-(IC3-N{slash}C_2-Pad25)") (class "Default")
      (node (ref "IC3") (pin "25") (pinfunction "N/C_2_25") (pintype "bidirectional"))
    )
    (net (code "142") (name "unconnected-(IC3-N{slash}C_3-Pad26)") (class "Default")
      (node (ref "IC3") (pin "26") (pinfunction "N/C_3_26") (pintype "bidirectional"))
    )
    (net (code "143") (name "unconnected-(IC3-N{slash}C_4-Pad34)") (class "Default")
      (node (ref "IC3") (pin "34") (pinfunction "N/C_4_34") (pintype "bidirectional"))
    )
  )
)
